# AAA_source.net
KiCad netlist of a schematic drawn in EAGLE
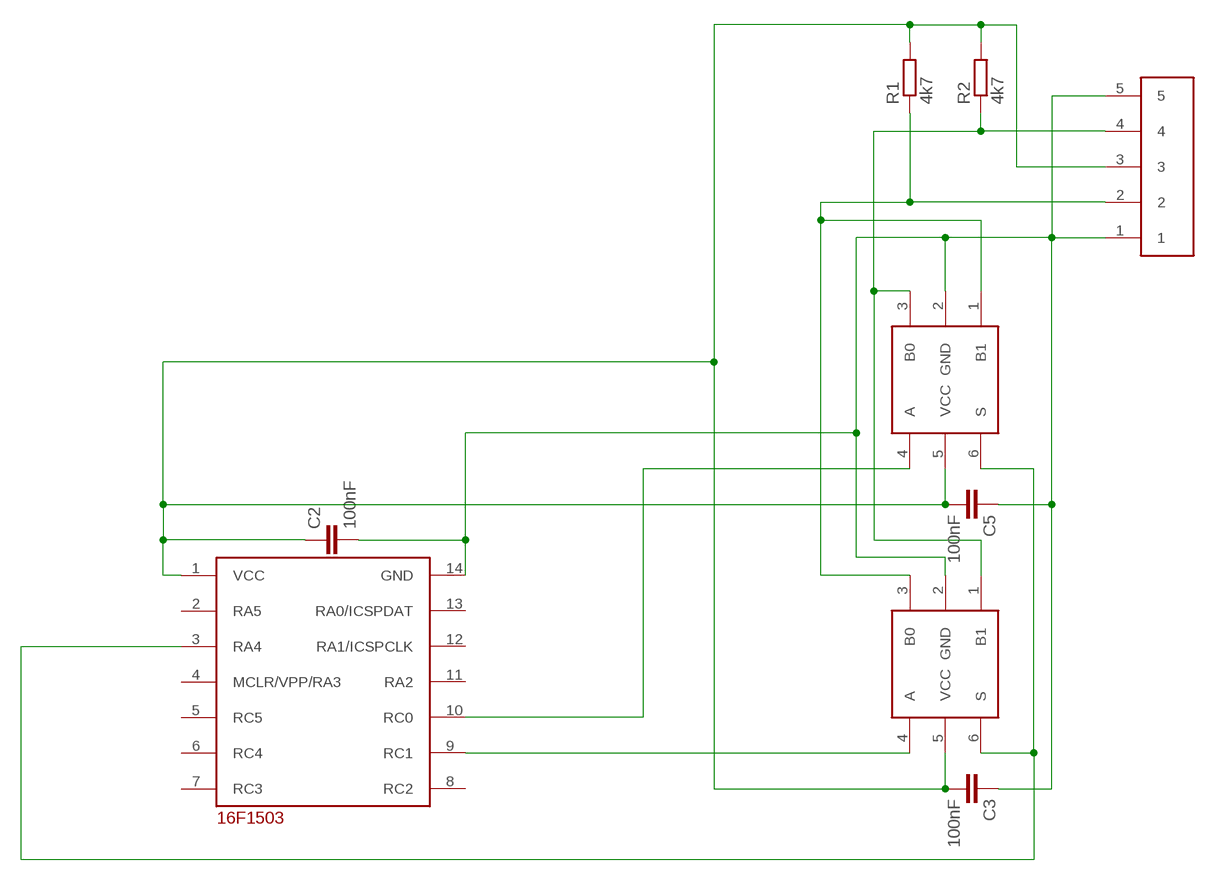
[diagram p0: schematic, sheet 1]

(export (version "E")
  (design (tool "Eeschema 10.0.6"))
  (components
    (comp (ref "C2")
      (value "100nF")
      (footprint "eagle-import:C0603")
      (libsource (lib "eagle-import") (part "C-EUC0603"))
    )
    (comp (ref "C3")
      (value "100nF")
      (footprint "eagle-import:C0603")
      (libsource (lib "eagle-import") (part "C-EUC0603"))
    )
    (comp (ref "C5")
      (value "100nF")
      (footprint "eagle-import:C0603")
      (libsource (lib "eagle-import") (part "C-EUC0603"))
    )
    (comp (ref "R1")
      (value "4k7")
      (footprint "eagle-import:R0603")
      (libsource (lib "eagle-import") (part "R-EU_R0603"))
    )
    (comp (ref "R2")
      (value "4k7")
      (footprint "eagle-import:R0603")
      (libsource (lib "eagle-import") (part "R-EU_R0603"))
    )
    (comp (ref "U$1")
      (value "16F103-TSSOP")
      (footprint "eagle-import:TSSOP14")
      (libsource (lib "eagle-import") (part "16F103-TSSOP"))
    )
    (comp (ref "U$5")
      (value "JUMPER5F-90")
      (footprint "eagle-import:JUMPER5F-90")
      (libsource (lib "eagle-import") (part "JUMPER5F-90"))
    )
    (comp (ref "U$6")
      (value "NC7SB3157P6X")
      (footprint "eagle-import:SC70-6L")
      (libsource (lib "eagle-import") (part "NC7SB3157P6X"))
    )
    (comp (ref "U$7")
      (value "NC7SB3157P6X")
      (footprint "eagle-import:SC70-6L")
      (libsource (lib "eagle-import") (part "NC7SB3157P6X"))
    )
  )
  (nets
    (net (code "1") (name "Net-(U$1-GND)") (class "Default")
      (node (ref "C2") (pin "2") (pinfunction "2_2") (pintype "passive"))
      (node (ref "C3") (pin "1") (pinfunction "1_1") (pintype "passive"))
      (node (ref "C5") (pin "1") (pinfunction "1_1") (pintype "passive"))
      (node (ref "U$1") (pin "14") (pinfunction "GND_14") (pintype "power_in"))
      (node (ref "U$5") (pin "1") (pinfunction "1_1") (pintype "bidirectional"))
      (node (ref "U$5") (pin "5") (pinfunction "5_5") (pintype "bidirectional"))
      (node (ref "U$6") (pin "2") (pinfunction "GND_2") (pintype "power_in"))
      (node (ref "U$7") (pin "2") (pinfunction "GND_2") (pintype "power_in"))
    )
    (net (code "2") (name "Net-(U$1-RA4)") (class "Default")
      (node (ref "U$1") (pin "3") (pinfunction "RA4_3") (pintype "bidirectional"))
      (node (ref "U$6") (pin "6") (pinfunction "S_6") (pintype "bidirectional"))
      (node (ref "U$7") (pin "6") (pinfunction "S_6") (pintype "bidirectional"))
    )
    (net (code "3") (name "Net-(U$1-RC0)") (class "Default")
      (node (ref "U$1") (pin "10") (pinfunction "RC0_10") (pintype "bidirectional"))
      (node (ref "U$6") (pin "4") (pinfunction "A_4") (pintype "bidirectional"))
    )
    (net (code "4") (name "Net-(U$1-RC1)") (class "Default")
      (node (ref "U$1") (pin "9") (pinfunction "RC1_9") (pintype "bidirectional"))
      (node (ref "U$7") (pin "4") (pinfunction "A_4") (pintype "bidirectional"))
    )
    (net (code "5") (name "Net-(U$1-VCC)") (class "Default")
      (node (ref "C2") (pin "1") (pinfunction "1_1") (pintype "passive"))
      (node (ref "C3") (pin "2") (pinfunction "2_2") (pintype "passive"))
      (node (ref "C5") (pin "2") (pinfunction "2_2") (pintype "passive"))
      (node (ref "R1") (pin "2") (pinfunction "2_2") (pintype "passive"))
      (node (ref "R2") (pin "2") (pinfunction "2_2") (pintype "passive"))
      (node (ref "U$1") (pin "1") (pinfunction "VCC_1") (pintype "power_in"))
      (node (ref "U$5") (pin "3") (pinfunction "3_3") (pintype "bidirectional"))
      (node (ref "U$6") (pin "5") (pinfunction "VCC_5") (pintype "power_in"))
      (node (ref "U$7") (pin "5") (pinfunction "VCC_5") (pintype "power_in"))
    )
    (net (code "6") (name "Net-(U$6-B0)") (class "Default")
      (node (ref "R2") (pin "1") (pinfunction "1_1") (pintype "passive"))
      (node (ref "U$5") (pin "4") (pinfunction "4_4") (pintype "bidirectional"))
      (node (ref "U$6") (pin "3") (pinfunction "B0_3") (pintype "bidirectional"))
      (node (ref "U$7") (pin "1") (pinfunction "B1_1") (pintype "bidirectional"))
    )
    (net (code "7") (name "Net-(U$6-B1)") (class "Default")
      (node (ref "R1") (pin "1") (pinfunction "1_1") (pintype "passive"))
      (node (ref "U$5") (pin "2") (pinfunction "2_2") (pintype "bidirectional"))
      (node (ref "U$6") (pin "1") (pinfunction "B1_1") (pintype "bidirectional"))
      (node (ref "U$7") (pin "3") (pinfunction "B0_3") (pintype "bidirectional"))
    )
    (net (code "8") (name "unconnected-(U$1-MCLR{slash}VPP{slash}RA3-Pad4)") (class "Default")
      (node (ref "U$1") (pin "4") (pinfunction "MCLR/VPP/RA3_4") (pintype "bidirectional"))
    )
    (net (code "9") (name "unconnected-(U$1-RA0{slash}ICSPDAT-Pad13)") (class "Default")
      (node (ref "U$1") (pin "13") (pinfunction "RA0/ICSPDAT_13") (pintype "bidirectional"))
    )
    (net (code "10") (name "unconnected-(U$1-RA1{slash}ICSPCLK-Pad12)") (class "Default")
      (node (ref "U$1") (pin "12") (pinfunction "RA1/ICSPCLK_12") (pintype "bidirectional"))
    )
    (net (code "11") (name "unconnected-(U$1-RA2-Pad11)") (class "Default")
      (node (ref "U$1") (pin "11") (pinfunction "RA2_11") (pintype "bidirectional"))
    )
    (net (code "12") (name "unconnected-(U$1-RA5-Pad2)") (class "Default")
      (node (ref "U$1") (pin "2") (pinfunction "RA5_2") (pintype "bidirectional"))
    )
    (net (code "13") (name "unconnected-(U$1-RC2-Pad8)") (class "Default")
      (node (ref "U$1") (pin "8") (pinfunction "RC2_8") (pintype "bidirectional"))
    )
    (net (code "14") (name "unconnected-(U$1-RC3-Pad7)") (class "Default")
      (node (ref "U$1") (pin "7") (pinfunction "RC3_7") (pintype "bidirectional"))
    )
    (net (code "15") (name "unconnected-(U$1-RC4-Pad6)") (class "Default")
      (node (ref "U$1") (pin "6") (pinfunction "RC4_6") (pintype "bidirectional"))
    )
    (net (code "16") (name "unconnected-(U$1-RC5-Pad5)") (class "Default")
      (node (ref "U$1") (pin "5") (pinfunction "RC5_5") (pintype "bidirectional"))
    )
  )
)
